# pulsometro.net
KiCad netlist of a schematic drawn in EAGLE
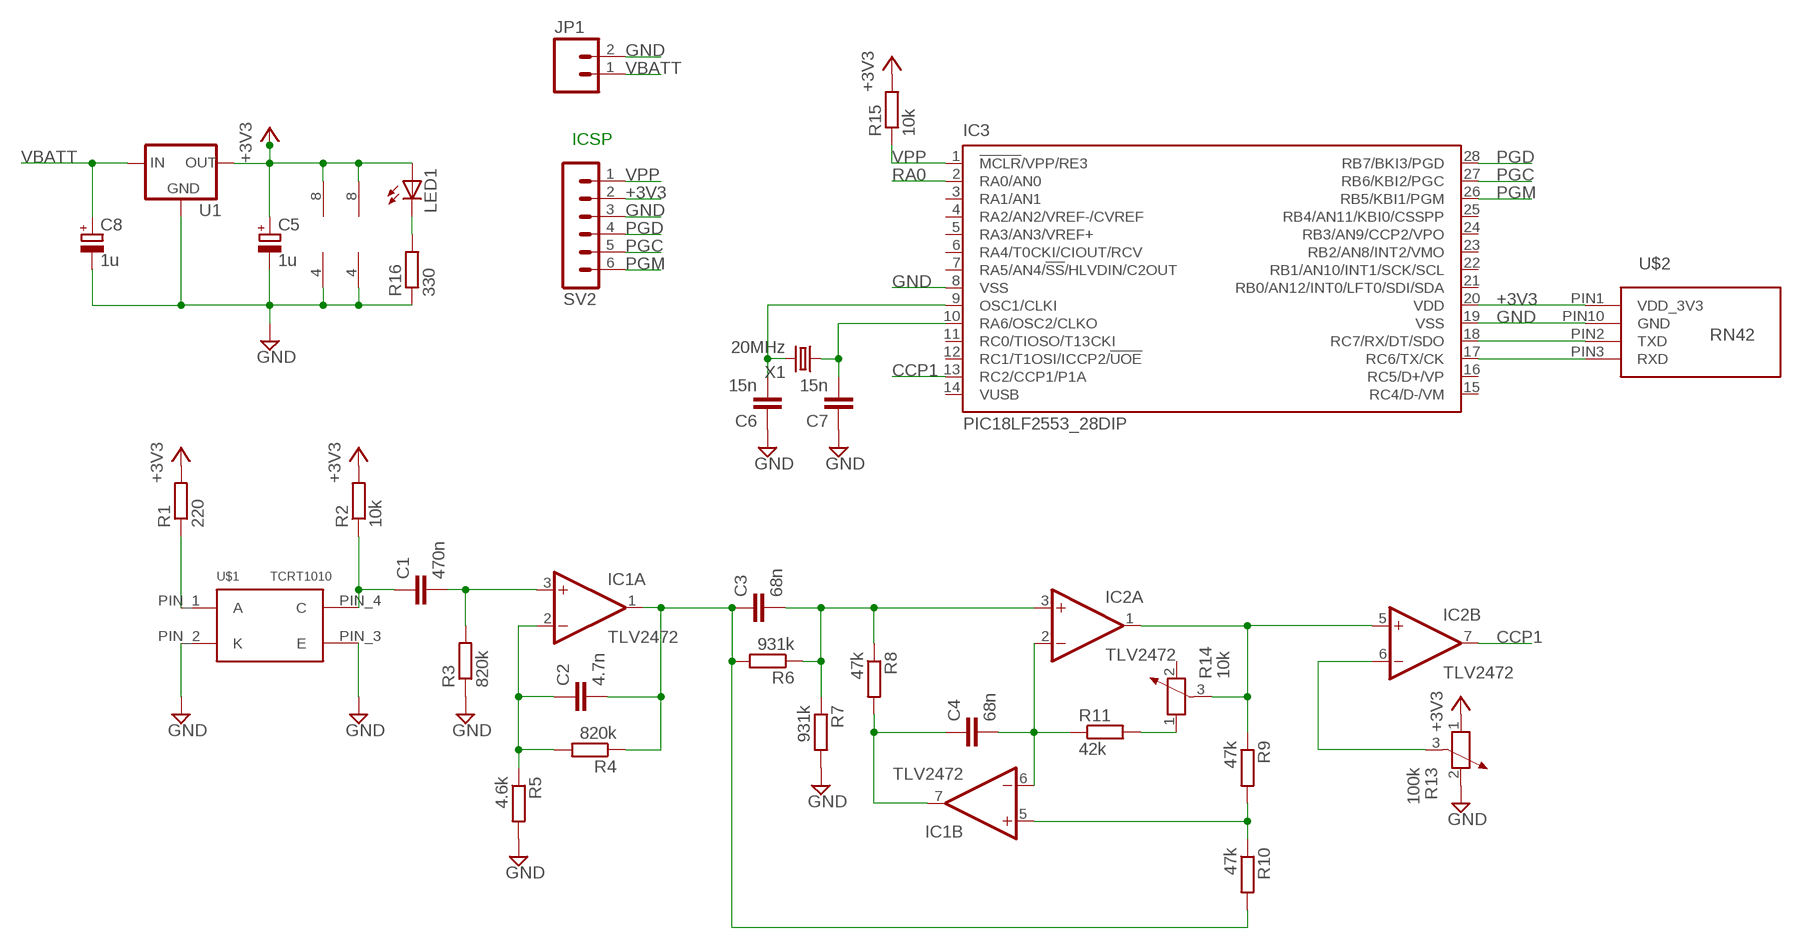
[diagram p0: schematic, sheet 1]

(export (version "E")
  (design (tool "Eeschema 10.0.6"))
  (components
    (comp (ref "C1")
      (value "470n")
      (footprint "eagle-import:C025-025X050")
      (libsource (lib "eagle-import") (part "C-EU025-025X050"))
    )
    (comp (ref "C2")
      (value "4.7n")
      (footprint "eagle-import:C025-025X050")
      (libsource (lib "eagle-import") (part "C-EU025-025X050"))
    )
    (comp (ref "C3")
      (value "68n")
      (footprint "eagle-import:C025-025X050")
      (libsource (lib "eagle-import") (part "C-EU025-025X050"))
    )
    (comp (ref "C4")
      (value "68n")
      (footprint "eagle-import:C025-025X050")
      (libsource (lib "eagle-import") (part "C-EU025-025X050"))
    )
    (comp (ref "C5")
      (value "1u")
      (footprint "eagle-import:E2,5-5")
      (libsource (lib "eagle-import") (part "CPOL-EUE2.5-5"))
    )
    (comp (ref "C6")
      (value "15n")
      (footprint "eagle-import:C025-025X050")
      (libsource (lib "eagle-import") (part "C-EU025-025X050"))
    )
    (comp (ref "C7")
      (value "15n")
      (footprint "eagle-import:C025-025X050")
      (libsource (lib "eagle-import") (part "C-EU025-025X050"))
    )
    (comp (ref "C8")
      (value "1u")
      (footprint "eagle-import:E2,5-5")
      (libsource (lib "eagle-import") (part "CPOL-EUE2.5-5"))
    )
    (comp (ref "IC1")
      (value "TLV2472")
      (footprint "eagle-import:DIL08")
      (libsource (lib "eagle-import") (part "LM358N"))
    )
    (comp (ref "IC2")
      (value "TLV2472")
      (footprint "eagle-import:DIL08")
      (libsource (lib "eagle-import") (part "LM358N"))
    )
    (comp (ref "IC3")
      (value "PIC18LF2553_28DIP")
      (footprint "eagle-import:DIL28-3")
      (fields (field (name "MF") "MICROCHIP") (field (name "MPN") "PIC18F2550-I/SP"))
      (libsource (lib "eagle-import") (part "PIC18F2_28DIP550"))
    )
    (comp (ref "JP1")
      (value "M02PTH")
      (footprint "eagle-import:1X02")
      (libsource (lib "eagle-import") (part "M02PTH"))
    )
    (comp (ref "LED1")
      (value "LED3MM")
      (footprint "eagle-import:LED3MM")
      (libsource (lib "eagle-import") (part "LED3MM"))
    )
    (comp (ref "R1")
      (value "220")
      (footprint "eagle-import:0204_7")
      (libsource (lib "eagle-import") (part "R-EU_0204/7"))
    )
    (comp (ref "R2")
      (value "10k")
      (footprint "eagle-import:0204_7")
      (libsource (lib "eagle-import") (part "R-EU_0204/7"))
    )
    (comp (ref "R3")
      (value "820k")
      (footprint "eagle-import:0204_7")
      (libsource (lib "eagle-import") (part "R-EU_0204/7"))
    )
    (comp (ref "R4")
      (value "820k")
      (footprint "eagle-import:0204_7")
      (libsource (lib "eagle-import") (part "R-EU_0204/7"))
    )
    (comp (ref "R5")
      (value "4.6k")
      (footprint "eagle-import:0204_7")
      (libsource (lib "eagle-import") (part "R-EU_0204/7"))
    )
    (comp (ref "R6")
      (value "931k")
      (footprint "eagle-import:0204_7")
      (libsource (lib "eagle-import") (part "R-EU_0204/7"))
    )
    (comp (ref "R7")
      (value "931k")
      (footprint "eagle-import:0204_7")
      (libsource (lib "eagle-import") (part "R-EU_0204/7"))
    )
    (comp (ref "R8")
      (value "47k")
      (footprint "eagle-import:0204_7")
      (libsource (lib "eagle-import") (part "R-EU_0204/7"))
    )
    (comp (ref "R9")
      (value "47k")
      (footprint "eagle-import:0204_7")
      (libsource (lib "eagle-import") (part "R-EU_0204/7"))
    )
    (comp (ref "R10")
      (value "47k")
      (footprint "eagle-import:0204_7")
      (libsource (lib "eagle-import") (part "R-EU_0204/7"))
    )
    (comp (ref "R11")
      (value "42k")
      (footprint "eagle-import:0204_7")
      (libsource (lib "eagle-import") (part "R-EU_0204/7"))
    )
    (comp (ref "R13")
      (value "100k")
      (footprint "eagle-import:PT-10")
      (libsource (lib "eagle-import") (part "POTENTIOMETER_PT-10"))
    )
    (comp (ref "R14")
      (value "10k")
      (footprint "eagle-import:PT-10")
      (libsource (lib "eagle-import") (part "POTENTIOMETER_PT-10"))
    )
    (comp (ref "R15")
      (value "10k")
      (footprint "eagle-import:0204_7")
      (libsource (lib "eagle-import") (part "R-EU_0204/7"))
    )
    (comp (ref "R16")
      (value "330")
      (footprint "eagle-import:0204_7")
      (libsource (lib "eagle-import") (part "R-EU_0204/7"))
    )
    (comp (ref "SV2")
      (value "MA06-1")
      (footprint "eagle-import:MA06-1")
      (libsource (lib "eagle-import") (part "MA06-1"))
    )
    (comp (ref "U$1")
      (value "TCRT1010")
      (footprint "eagle-import:TCRT1010")
      (libsource (lib "eagle-import") (part "TCRT1010"))
    )
    (comp (ref "U$2")
      (value "RN42")
      (footprint "eagle-import:2X10-2MMSOCKET")
      (libsource (lib "eagle-import") (part "RN42"))
    )
    (comp (ref "U1")
      (value "V_REG_78XXTO-92_UNTESTED")
      (footprint "eagle-import:TO-92")
      (libsource (lib "eagle-import") (part "V_REG_78XXTO-92_UNTESTED"))
    )
    (comp (ref "X1")
      (value "20MHz")
      (footprint "eagle-import:HC49")
      (libsource (lib "eagle-import") (part "CRYSTALS-NOGND-HC49"))
    )
  )
  (nets
    (net (code "1") (name "+3V3") (class "Default")
      (node (ref "C5") (pin "+") (pinfunction "+_+") (pintype "passive"))
      (node (ref "IC1") (pin "8") (pinfunction "V+_8") (pintype "power_in"))
      (node (ref "IC2") (pin "8") (pinfunction "V+_8") (pintype "power_in"))
      (node (ref "IC3") (pin "20") (pinfunction "VDD_20") (pintype "power_in"))
      (node (ref "LED1") (pin "A") (pinfunction "A_A") (pintype "passive"))
      (node (ref "R1") (pin "2") (pinfunction "2_2") (pintype "passive"))
      (node (ref "R13") (pin "1") (pinfunction "1_1") (pintype "passive"))
      (node (ref "R15") (pin "2") (pinfunction "2_2") (pintype "passive"))
      (node (ref "R2") (pin "2") (pinfunction "2_2") (pintype "passive"))
      (node (ref "SV2") (pin "2") (pinfunction "2_2") (pintype "passive"))
      (node (ref "U$2") (pin "PIN1") (pinfunction "VDD_3V3_PIN1") (pintype "power_in"))
      (node (ref "U1") (pin "3") (pinfunction "OUT_3") (pintype "passive"))
    )
    (net (code "2") (name "/CCP1") (class "Default")
      (node (ref "IC2") (pin "7") (pinfunction "OUT_7") (pintype "output"))
      (node (ref "IC3") (pin "13") (pinfunction "RC2/CCP1/P1A_13") (pintype "bidirectional"))
    )
    (net (code "3") (name "/PGC") (class "Default")
      (node (ref "IC3") (pin "27") (pinfunction "RB6/KBI2/PGC_27") (pintype "bidirectional"))
      (node (ref "SV2") (pin "5") (pinfunction "5_5") (pintype "passive"))
    )
    (net (code "4") (name "/PGD") (class "Default")
      (node (ref "IC3") (pin "28") (pinfunction "RB7/BKI3/PGD_28") (pintype "bidirectional"))
      (node (ref "SV2") (pin "4") (pinfunction "4_4") (pintype "passive"))
    )
    (net (code "5") (name "/PGM") (class "Default")
      (node (ref "IC3") (pin "26") (pinfunction "RB5/KBI1/PGM_26") (pintype "bidirectional"))
      (node (ref "SV2") (pin "6") (pinfunction "6_6") (pintype "passive"))
    )
    (net (code "6") (name "/RA0") (class "Default")
      (node (ref "IC3") (pin "2") (pinfunction "RA0/AN0_2") (pintype "bidirectional"))
    )
    (net (code "7") (name "/VBATT") (class "Default")
      (node (ref "C8") (pin "+") (pinfunction "+_+") (pintype "passive"))
      (node (ref "JP1") (pin "1") (pinfunction "1_1") (pintype "passive"))
      (node (ref "U1") (pin "2") (pinfunction "IN_2") (pintype "input"))
    )
    (net (code "8") (name "/VPP") (class "Default")
      (node (ref "IC3") (pin "1") (pinfunction "~{MCLR}/VPP/RE3_1") (pintype "input"))
      (node (ref "R15") (pin "1") (pinfunction "1_1") (pintype "passive"))
      (node (ref "SV2") (pin "1") (pinfunction "1_1") (pintype "passive"))
    )
    (net (code "9") (name "GND") (class "Default")
      (node (ref "C5") (pin "-") (pinfunction "-_-") (pintype "passive"))
      (node (ref "C6") (pin "1") (pinfunction "1_1") (pintype "passive"))
      (node (ref "C7") (pin "1") (pinfunction "1_1") (pintype "passive"))
      (node (ref "C8") (pin "-") (pinfunction "-_-") (pintype "passive"))
      (node (ref "IC1") (pin "4") (pinfunction "V-_4") (pintype "power_in"))
      (node (ref "IC2") (pin "4") (pinfunction "V-_4") (pintype "power_in"))
      (node (ref "IC3") (pin "19") (pinfunction "VSS_19") (pintype "power_in"))
      (node (ref "IC3") (pin "8") (pinfunction "VSS_8") (pintype "power_in"))
      (node (ref "JP1") (pin "2") (pinfunction "2_2") (pintype "passive"))
      (node (ref "R13") (pin "2") (pinfunction "2_2") (pintype "passive"))
      (node (ref "R16") (pin "1") (pinfunction "1_1") (pintype "passive"))
      (node (ref "R3") (pin "1") (pinfunction "1_1") (pintype "passive"))
      (node (ref "R5") (pin "2") (pinfunction "2_2") (pintype "passive"))
      (node (ref "R7") (pin "2") (pinfunction "2_2") (pintype "passive"))
      (node (ref "SV2") (pin "3") (pinfunction "3_3") (pintype "passive"))
      (node (ref "U$1") (pin "PIN_2") (pinfunction "K_PIN_2") (pintype "output"))
      (node (ref "U$1") (pin "PIN_3") (pinfunction "E_PIN_3") (pintype "output"))
      (node (ref "U$2") (pin "PIN10") (pinfunction "GND_PIN10") (pintype "power_in"))
      (node (ref "U1") (pin "1") (pinfunction "GND_1") (pintype "input"))
    )
    (net (code "10") (name "Net-(IC1A-+IN)") (class "Default")
      (node (ref "C1") (pin "2") (pinfunction "2_2") (pintype "passive"))
      (node (ref "IC1") (pin "3") (pinfunction "+IN_3") (pintype "input"))
      (node (ref "R3") (pin "2") (pinfunction "2_2") (pintype "passive"))
    )
    (net (code "11") (name "Net-(IC1A--IN)") (class "Default")
      (node (ref "C2") (pin "1") (pinfunction "1_1") (pintype "passive"))
      (node (ref "IC1") (pin "2") (pinfunction "-IN_2") (pintype "input"))
      (node (ref "R4") (pin "2") (pinfunction "2_2") (pintype "passive"))
      (node (ref "R5") (pin "1") (pinfunction "1_1") (pintype "passive"))
    )
    (net (code "12") (name "Net-(IC1A-OUT)") (class "Default")
      (node (ref "C2") (pin "2") (pinfunction "2_2") (pintype "passive"))
      (node (ref "C3") (pin "1") (pinfunction "1_1") (pintype "passive"))
      (node (ref "IC1") (pin "1") (pinfunction "OUT_1") (pintype "output"))
      (node (ref "R10") (pin "2") (pinfunction "2_2") (pintype "passive"))
      (node (ref "R4") (pin "1") (pinfunction "1_1") (pintype "passive"))
      (node (ref "R6") (pin "2") (pinfunction "2_2") (pintype "passive"))
    )
    (net (code "13") (name "Net-(IC1B-+IN)") (class "Default")
      (node (ref "IC1") (pin "5") (pinfunction "+IN_5") (pintype "input"))
      (node (ref "R10") (pin "1") (pinfunction "1_1") (pintype "passive"))
      (node (ref "R9") (pin "2") (pinfunction "2_2") (pintype "passive"))
    )
    (net (code "14") (name "Net-(IC1B--IN)") (class "Default")
      (node (ref "C4") (pin "2") (pinfunction "2_2") (pintype "passive"))
      (node (ref "IC1") (pin "6") (pinfunction "-IN_6") (pintype "input"))
      (node (ref "IC2") (pin "2") (pinfunction "-IN_2") (pintype "input"))
      (node (ref "R11") (pin "1") (pinfunction "1_1") (pintype "passive"))
    )
    (net (code "15") (name "Net-(IC1B-OUT)") (class "Default")
      (node (ref "C4") (pin "1") (pinfunction "1_1") (pintype "passive"))
      (node (ref "IC1") (pin "7") (pinfunction "OUT_7") (pintype "output"))
      (node (ref "R8") (pin "2") (pinfunction "2_2") (pintype "passive"))
    )
    (net (code "16") (name "Net-(IC2A-+IN)") (class "Default")
      (node (ref "C3") (pin "2") (pinfunction "2_2") (pintype "passive"))
      (node (ref "IC2") (pin "3") (pinfunction "+IN_3") (pintype "input"))
      (node (ref "R6") (pin "1") (pinfunction "1_1") (pintype "passive"))
      (node (ref "R7") (pin "1") (pinfunction "1_1") (pintype "passive"))
      (node (ref "R8") (pin "1") (pinfunction "1_1") (pintype "passive"))
    )
    (net (code "17") (name "Net-(IC2A-OUT)") (class "Default")
      (node (ref "IC2") (pin "1") (pinfunction "OUT_1") (pintype "output"))
      (node (ref "IC2") (pin "5") (pinfunction "+IN_5") (pintype "input"))
      (node (ref "R14") (pin "3") (pinfunction "3_3") (pintype "passive"))
      (node (ref "R9") (pin "1") (pinfunction "1_1") (pintype "passive"))
    )
    (net (code "18") (name "Net-(IC2B--IN)") (class "Default")
      (node (ref "IC2") (pin "6") (pinfunction "-IN_6") (pintype "input"))
      (node (ref "R13") (pin "3") (pinfunction "3_3") (pintype "passive"))
    )
    (net (code "19") (name "Net-(IC3-OSC1{slash}CLKI)") (class "Default")
      (node (ref "C6") (pin "2") (pinfunction "2_2") (pintype "passive"))
      (node (ref "IC3") (pin "9") (pinfunction "OSC1/CLKI_9") (pintype "input"))
      (node (ref "X1") (pin "2") (pinfunction "2_2") (pintype "passive"))
    )
    (net (code "20") (name "Net-(IC3-RA6{slash}OSC2{slash}CLKO)") (class "Default")
      (node (ref "C7") (pin "2") (pinfunction "2_2") (pintype "passive"))
      (node (ref "IC3") (pin "10") (pinfunction "RA6/OSC2/CLKO_10") (pintype "output"))
      (node (ref "X1") (pin "1") (pinfunction "1_1") (pintype "passive"))
    )
    (net (code "21") (name "Net-(IC3-RC6{slash}TX{slash}CK)") (class "Default")
      (node (ref "IC3") (pin "17") (pinfunction "RC6/TX/CK_17") (pintype "bidirectional"))
      (node (ref "U$2") (pin "PIN3") (pinfunction "RXD_PIN3") (pintype "input"))
    )
    (net (code "22") (name "Net-(IC3-RC7{slash}RX{slash}DT{slash}SDO)") (class "Default")
      (node (ref "IC3") (pin "18") (pinfunction "RC7/RX/DT/SDO_18") (pintype "bidirectional"))
      (node (ref "U$2") (pin "PIN2") (pinfunction "TXD_PIN2") (pintype "output"))
    )
    (net (code "23") (name "Net-(LED1-C)") (class "Default")
      (node (ref "LED1") (pin "K") (pinfunction "C_K") (pintype "passive"))
      (node (ref "R16") (pin "2") (pinfunction "2_2") (pintype "passive"))
    )
    (net (code "24") (name "Net-(R11-Pad2)") (class "Default")
      (node (ref "R11") (pin "2") (pinfunction "2_2") (pintype "passive"))
      (node (ref "R14") (pin "1") (pinfunction "1_1") (pintype "passive"))
    )
    (net (code "25") (name "Net-(U$1-A)") (class "Default")
      (node (ref "R1") (pin "1") (pinfunction "1_1") (pintype "passive"))
      (node (ref "U$1") (pin "PIN_1") (pinfunction "A_PIN_1") (pintype "input"))
    )
    (net (code "26") (name "Net-(U$1-C)") (class "Default")
      (node (ref "C1") (pin "1") (pinfunction "1_1") (pintype "passive"))
      (node (ref "R2") (pin "1") (pinfunction "1_1") (pintype "passive"))
      (node (ref "U$1") (pin "PIN_4") (pinfunction "C_PIN_4") (pintype "input"))
    )
    (net (code "27") (name "unconnected-(IC3-RA1{slash}AN1-Pad3)") (class "Default")
      (node (ref "IC3") (pin "3") (pinfunction "RA1/AN1_3") (pintype "bidirectional"))
    )
    (net (code "28") (name "unconnected-(IC3-RA2{slash}AN2{slash}VREF-{slash}CVREF-Pad4)") (class "Default")
      (node (ref "IC3") (pin "4") (pinfunction "RA2/AN2/VREF-/CVREF_4") (pintype "bidirectional"))
    )
    (net (code "29") (name "unconnected-(IC3-RA3{slash}AN3{slash}VREF+-Pad5)") (class "Default")
      (node (ref "IC3") (pin "5") (pinfunction "RA3/AN3/VREF+_5") (pintype "bidirectional"))
    )
    (net (code "30") (name "unconnected-(IC3-RA4{slash}T0CKI{slash}CIOUT{slash}RCV-Pad6)") (class "Default")
      (node (ref "IC3") (pin "6") (pinfunction "RA4/T0CKI/CIOUT/RCV_6") (pintype "bidirectional"))
    )
    (net (code "31") (name "unconnected-(IC3-RA5{slash}AN4{slash}~{SS}{slash}HLVDIN{slash}C2OUT-Pad7)") (class "Default")
      (node (ref "IC3") (pin "7") (pinfunction "RA5/AN4/~{SS}/HLVDIN/C2OUT_7") (pintype "bidirectional"))
    )
    (net (code "32") (name "unconnected-(IC3-RB0{slash}AN12{slash}INT0{slash}LFT0{slash}SDI{slash}SDA-Pad21)") (class "Default")
      (node (ref "IC3") (pin "21") (pinfunction "RB0/AN12/INT0/LFT0/SDI/SDA_21") (pintype "bidirectional"))
    )
    (net (code "33") (name "unconnected-(IC3-RB1{slash}AN10{slash}INT1{slash}SCK{slash}SCL-Pad22)") (class "Default")
      (node (ref "IC3") (pin "22") (pinfunction "RB1/AN10/INT1/SCK/SCL_22") (pintype "bidirectional"))
    )
    (net (code "34") (name "unconnected-(IC3-RB2{slash}AN8{slash}INT2{slash}VMO-Pad23)") (class "Default")
      (node (ref "IC3") (pin "23") (pinfunction "RB2/AN8/INT2/VMO_23") (pintype "bidirectional"))
    )
    (net (code "35") (name "unconnected-(IC3-RB3{slash}AN9{slash}CCP2{slash}VPO-Pad24)") (class "Default")
      (node (ref "IC3") (pin "24") (pinfunction "RB3/AN9/CCP2/VPO_24") (pintype "bidirectional"))
    )
    (net (code "36") (name "unconnected-(IC3-RB4{slash}AN11{slash}KBI0{slash}CSSPP-Pad25)") (class "Default")
      (node (ref "IC3") (pin "25") (pinfunction "RB4/AN11/KBI0/CSSPP_25") (pintype "bidirectional"))
    )
    (net (code "37") (name "unconnected-(IC3-RC0{slash}TIOSO{slash}T13CKI-Pad11)") (class "Default")
      (node (ref "IC3") (pin "11") (pinfunction "RC0/TIOSO/T13CKI_11") (pintype "bidirectional"))
    )
    (net (code "38") (name "unconnected-(IC3-RC1{slash}T1OSI{slash}ICCP2{slash}~{UOE}-Pad12)") (class "Default")
      (node (ref "IC3") (pin "12") (pinfunction "RC1/T1OSI/ICCP2/~{UOE}_12") (pintype "bidirectional"))
    )
    (net (code "39") (name "unconnected-(IC3-RC4{slash}D-{slash}VM-Pad15)") (class "Default")
      (node (ref "IC3") (pin "15") (pinfunction "RC4/D-/VM_15") (pintype "bidirectional"))
    )
    (net (code "40") (name "unconnected-(IC3-RC5{slash}D+{slash}VP-Pad16)") (class "Default")
      (node (ref "IC3") (pin "16") (pinfunction "RC5/D+/VP_16") (pintype "bidirectional"))
    )
    (net (code "41") (name "unconnected-(IC3-VUSB-Pad14)") (class "Default")
      (node (ref "IC3") (pin "14") (pinfunction "VUSB_14") (pintype "bidirectional"))
    )
    (net (code "42") (name "unconnected-(R14-Pad2)") (class "Default")
      (node (ref "R14") (pin "2") (pinfunction "2_2") (pintype "passive"))
    )
  )
)
